# soldering.net
KiCad netlist of a schematic drawn in Altium Designer
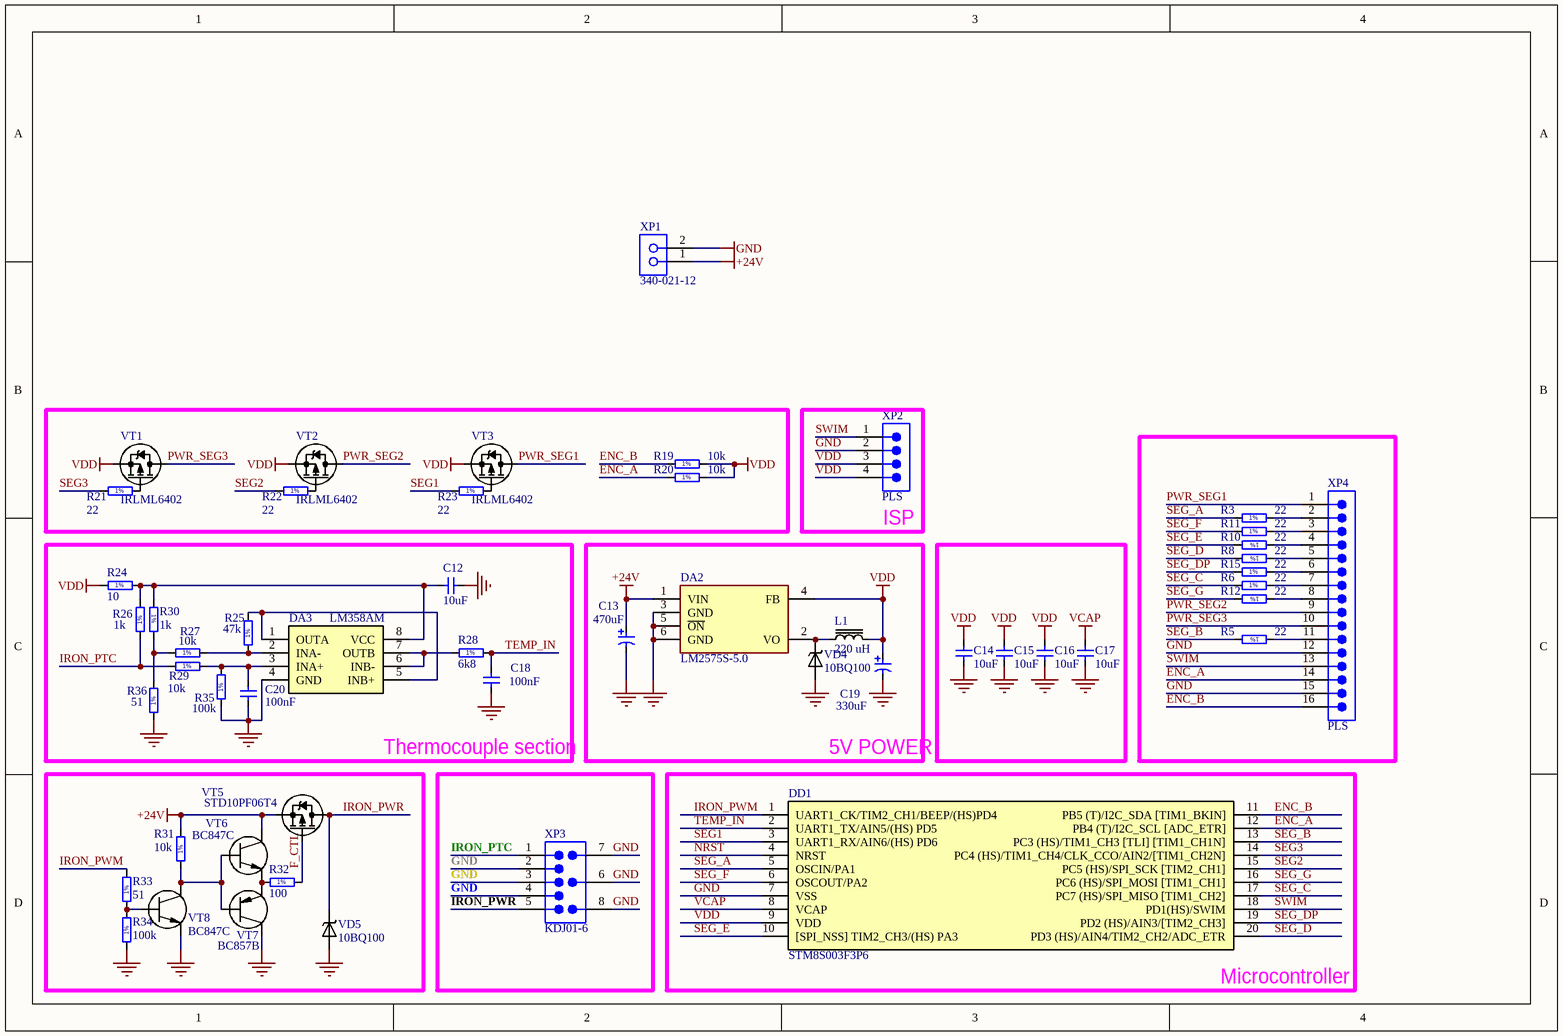
[diagram p0: soldering.SchDoc]

(export (version "E")
  (design (tool "Eeschema 10.0.6"))
  (components
    (comp (ref "C12")
      (value "10uF")
      (footprint "CAP0805R")
      (description "SMD 0805 Capacitor")
      (fields
        (field (name "PART NUMBER") "CC0805_10UF_10V_10%_X7R")
        (field (name "VOLTAGE") "10V")
        (field (name "AUTHOR") "I. Kuznetsov")
      )
      (libsource (lib "Capacitor") (part "CAP_NON_POLAR"))
    )
    (comp (ref "C13")
      (value "470uF")
      (footprint "CAP_EL_10_19_VERT")
      (fields (field (name "PART NUMBER") "SH050M0470B5S-1019 (VERT MOUNTED)") (field (name "VOLTAGE") "50V"))
      (libsource (lib "Capacitor") (part "CAP_POLAR"))
    )
    (comp (ref "C14")
      (value "10uF")
      (footprint "CAP0805R")
      (description "SMD 0805 Capacitor")
      (fields
        (field (name "PART NUMBER") "CC0805_10UF_10V_10%_X7R")
        (field (name "VOLTAGE") "10V")
        (field (name "AUTHOR") "I. Kuznetsov")
      )
      (libsource (lib "Capacitor") (part "CAP_NON_POLAR"))
    )
    (comp (ref "C15")
      (value "10uF")
      (footprint "CAP0805R")
      (description "SMD 0805 Capacitor")
      (fields
        (field (name "PART NUMBER") "CC0805_10UF_10V_10%_X7R")
        (field (name "VOLTAGE") "10V")
        (field (name "AUTHOR") "I. Kuznetsov")
      )
      (libsource (lib "Capacitor") (part "CAP_NON_POLAR"))
    )
    (comp (ref "C16")
      (value "10uF")
      (footprint "CAP0805R")
      (description "SMD 0805 Capacitor")
      (fields
        (field (name "PART NUMBER") "CC0805_10UF_10V_10%_X7R")
        (field (name "VOLTAGE") "10V")
        (field (name "AUTHOR") "I. Kuznetsov")
      )
      (libsource (lib "Capacitor") (part "CAP_NON_POLAR"))
    )
    (comp (ref "C17")
      (value "10uF")
      (footprint "CAP0805R")
      (description "SMD 0805 Capacitor")
      (fields
        (field (name "PART NUMBER") "CC0805_10UF_10V_10%_X7R")
        (field (name "VOLTAGE") "10V")
        (field (name "AUTHOR") "I. Kuznetsov")
      )
      (libsource (lib "Capacitor") (part "CAP_NON_POLAR"))
    )
    (comp (ref "C18")
      (value "100nF")
      (footprint "CAP0805R")
      (description "SMD 0805 Capacitor")
      (fields
        (field (name "PART NUMBER") "CC0805_100NF_50V_10%_X7R")
        (field (name "VOLTAGE") "50V")
        (field (name "AUTHOR") "I. Kuznetsov")
      )
      (libsource (lib "Capacitor") (part "CAP_NON_POLAR"))
    )
    (comp (ref "C19")
      (value "330uF")
      (footprint "TAN_D")
      (fields (field (name "PART NUMBER") "T495D337M010AHE100") (field (name "VOLTAGE") "10V"))
      (libsource (lib "Capacitor") (part "CAP_POLAR"))
    )
    (comp (ref "C20")
      (value "100nF")
      (footprint "CAP0805R")
      (description "SMD 0805 Capacitor")
      (fields
        (field (name "PART NUMBER") "CC0805_100NF_50V_10%_X7R")
        (field (name "VOLTAGE") "50V")
        (field (name "AUTHOR") "I. Kuznetsov")
      )
      (libsource (lib "Capacitor") (part "CAP_NON_POLAR"))
    )
    (comp (ref "DA2")
      (value "LM2575S-5.0")
      (footprint "TO-263-5")
      (fields (field (name "MANUFACTURER") "TI") (field (name "AUTHOR") "I. Kuznetsov"))
      (libsource (lib "IC And Semiconductor") (part "LM2575S"))
    )
    (comp (ref "DA3")
      (value "OP Amp")
      (footprint "SOP8")
      (fields (field (name "PARTNUMBER") "LM358AM"))
      (libsource (lib "tonometr") (part "LM358AM"))
    )
    (comp (ref "DD1")
      (value "8 Bit MCU")
      (footprint "TSSOP20")
      (description "8 Bit MCU (STmicroelectronics)")
      (fields (field (name "PARTNUMBER") "STM8S003F3P6"))
      (libsource (lib "soldering") (part "STM8S003F3P6"))
    )
    (comp (ref "L1")
      (value "220 uH")
      (footprint "SL1016")
      (fields (field (name "PART NUMBER") "SL1016T-4R7K-B-N") (field (name "TOLERANCE") "± 10%"))
      (libsource (lib "Transformer") (part "Core_Inductor"))
    )
    (comp (ref "R3")
      (value "22")
      (footprint "RES0805R")
      (fields
        (field (name "PART NUMBER") "R0805_22R_1%_0.125W_100PPM")
        (field (name "POWER") "0.125W")
        (field (name "TOLERANCE") "±1%")
        (field (name "AUTHOR") "CERN DEM JLC")
      )
      (libsource (lib "Resistor") (part "Resistor - 1%"))
    )
    (comp (ref "R5")
      (value "22")
      (footprint "RES0805R")
      (fields
        (field (name "PART NUMBER") "R0805_22R_1%_0.125W_100PPM")
        (field (name "POWER") "0.125W")
        (field (name "TOLERANCE") "±1%")
        (field (name "AUTHOR") "CERN DEM JLC")
      )
      (libsource (lib "Resistor") (part "Resistor - 1%"))
    )
    (comp (ref "R6")
      (value "22")
      (footprint "RES0805R")
      (fields
        (field (name "PART NUMBER") "R0805_22R_1%_0.125W_100PPM")
        (field (name "POWER") "0.125W")
        (field (name "TOLERANCE") "±1%")
        (field (name "AUTHOR") "CERN DEM JLC")
      )
      (libsource (lib "Resistor") (part "Resistor - 1%"))
    )
    (comp (ref "R8")
      (value "22")
      (footprint "RES0805R")
      (fields
        (field (name "PART NUMBER") "R0805_22R_1%_0.125W_100PPM")
        (field (name "POWER") "0.125W")
        (field (name "TOLERANCE") "±1%")
        (field (name "AUTHOR") "CERN DEM JLC")
      )
      (libsource (lib "Resistor") (part "Resistor - 1%"))
    )
    (comp (ref "R10")
      (value "22")
      (footprint "RES0805R")
      (fields
        (field (name "PART NUMBER") "R0805_22R_1%_0.125W_100PPM")
        (field (name "POWER") "0.125W")
        (field (name "TOLERANCE") "±1%")
        (field (name "AUTHOR") "CERN DEM JLC")
      )
      (libsource (lib "Resistor") (part "Resistor - 1%"))
    )
    (comp (ref "R11")
      (value "22")
      (footprint "RES0805R")
      (fields
        (field (name "PART NUMBER") "R0805_22R_1%_0.125W_100PPM")
        (field (name "POWER") "0.125W")
        (field (name "TOLERANCE") "±1%")
        (field (name "AUTHOR") "CERN DEM JLC")
      )
      (libsource (lib "Resistor") (part "Resistor - 1%"))
    )
    (comp (ref "R12")
      (value "22")
      (footprint "RES0805R")
      (fields
        (field (name "PART NUMBER") "R0805_22R_1%_0.125W_100PPM")
        (field (name "POWER") "0.125W")
        (field (name "TOLERANCE") "±1%")
        (field (name "AUTHOR") "CERN DEM JLC")
      )
      (libsource (lib "Resistor") (part "Resistor - 1%"))
    )
    (comp (ref "R15")
      (value "22")
      (footprint "RES0805R")
      (fields
        (field (name "PART NUMBER") "R0805_22R_1%_0.125W_100PPM")
        (field (name "POWER") "0.125W")
        (field (name "TOLERANCE") "±1%")
        (field (name "AUTHOR") "CERN DEM JLC")
      )
      (libsource (lib "Resistor") (part "Resistor - 1%"))
    )
    (comp (ref "R19")
      (value "10k")
      (footprint "RES0805R")
      (fields
        (field (name "PART NUMBER") "R0805_10K_1%_0.125W_100PPM")
        (field (name "POWER") "0.125W")
        (field (name "TOLERANCE") "±1%")
        (field (name "AUTHOR") "CERN DEM JLC")
      )
      (libsource (lib "Resistor") (part "Resistor - 1%"))
    )
    (comp (ref "R20")
      (value "10k")
      (footprint "RES0805R")
      (fields
        (field (name "PART NUMBER") "R0805_10K_1%_0.125W_100PPM")
        (field (name "POWER") "0.125W")
        (field (name "TOLERANCE") "±1%")
        (field (name "AUTHOR") "CERN DEM JLC")
      )
      (libsource (lib "Resistor") (part "Resistor - 1%"))
    )
    (comp (ref "R21")
      (value "22")
      (footprint "RES0805R")
      (fields
        (field (name "PART NUMBER") "R0805_22R_1%_0.125W_100PPM")
        (field (name "POWER") "0.125W")
        (field (name "TOLERANCE") "±1%")
        (field (name "AUTHOR") "CERN DEM JLC")
      )
      (libsource (lib "Resistor") (part "Resistor - 1%"))
    )
    (comp (ref "R22")
      (value "22")
      (footprint "RES0805R")
      (fields
        (field (name "PART NUMBER") "R0805_22R_1%_0.125W_100PPM")
        (field (name "POWER") "0.125W")
        (field (name "TOLERANCE") "±1%")
        (field (name "AUTHOR") "CERN DEM JLC")
      )
      (libsource (lib "Resistor") (part "Resistor - 1%"))
    )
    (comp (ref "R23")
      (value "22")
      (footprint "RES0805R")
      (fields
        (field (name "PART NUMBER") "R0805_22R_1%_0.125W_100PPM")
        (field (name "POWER") "0.125W")
        (field (name "TOLERANCE") "±1%")
        (field (name "AUTHOR") "CERN DEM JLC")
      )
      (libsource (lib "Resistor") (part "Resistor - 1%"))
    )
    (comp (ref "R24")
      (value "10")
      (footprint "RES0805R")
      (fields
        (field (name "PART NUMBER") "R0805_10R_1%_0.125W_200PPM")
        (field (name "POWER") "0.125W")
        (field (name "TOLERANCE") "±1%")
        (field (name "AUTHOR") "CERN DEM JLC")
      )
      (libsource (lib "Resistor") (part "Resistor - 1%"))
    )
    (comp (ref "R25")
      (value "47k")
      (footprint "RES0805R")
      (fields
        (field (name "PART NUMBER") "R0805_47K_1%_0.125W_100PPM")
        (field (name "POWER") "0.125W")
        (field (name "TOLERANCE") "±1%")
        (field (name "AUTHOR") "CERN DEM JLC")
      )
      (libsource (lib "Resistor") (part "Resistor - 1%"))
    )
    (comp (ref "R26")
      (value "1k")
      (footprint "RES0805R")
      (fields
        (field (name "PART NUMBER") "R0805_1K_1%_0.125W_100PPM")
        (field (name "POWER") "0.125W")
        (field (name "TOLERANCE") "±1%")
        (field (name "AUTHOR") "CERN DEM JLC")
      )
      (libsource (lib "Resistor") (part "Resistor - 1%"))
    )
    (comp (ref "R27")
      (value "10k")
      (footprint "RES0805R")
      (fields
        (field (name "PART NUMBER") "R0805_10K_1%_0.125W_100PPM")
        (field (name "POWER") "0.125W")
        (field (name "TOLERANCE") "±1%")
        (field (name "AUTHOR") "CERN DEM JLC")
      )
      (libsource (lib "Resistor") (part "Resistor - 1%"))
    )
    (comp (ref "R28")
      (value "6k8")
      (footprint "RES0805R")
      (fields
        (field (name "PART NUMBER") "R0805_6K8_1%_0.125W_100PPM")
        (field (name "POWER") "0.125W")
        (field (name "TOLERANCE") "±1%")
        (field (name "AUTHOR") "CERN DEM JLC")
      )
      (libsource (lib "Resistor") (part "Resistor - 1%"))
    )
    (comp (ref "R29")
      (value "10k")
      (footprint "RES0805R")
      (fields
        (field (name "PART NUMBER") "R0805_10K_1%_0.125W_100PPM")
        (field (name "POWER") "0.125W")
        (field (name "TOLERANCE") "±1%")
        (field (name "AUTHOR") "CERN DEM JLC")
      )
      (libsource (lib "Resistor") (part "Resistor - 1%"))
    )
    (comp (ref "R30")
      (value "1k")
      (footprint "RES0805R")
      (fields
        (field (name "PART NUMBER") "R0805_1K_1%_0.125W_100PPM")
        (field (name "POWER") "0.125W")
        (field (name "TOLERANCE") "±1%")
        (field (name "AUTHOR") "CERN DEM JLC")
      )
      (libsource (lib "Resistor") (part "Resistor - 1%"))
    )
    (comp (ref "R31")
      (value "10k")
      (footprint "RES0805R")
      (fields
        (field (name "PART NUMBER") "R0805_10K_1%_0.125W_100PPM")
        (field (name "POWER") "0.125W")
        (field (name "TOLERANCE") "±1%")
        (field (name "AUTHOR") "CERN DEM JLC")
      )
      (libsource (lib "Resistor") (part "Resistor - 1%"))
    )
    (comp (ref "R32")
      (value "100")
      (footprint "RES0805R")
      (fields
        (field (name "PART NUMBER") "R0805_100R_1%_0.125W_100PPM")
        (field (name "POWER") "0.125W")
        (field (name "TOLERANCE") "±1%")
        (field (name "AUTHOR") "CERN DEM JLC")
      )
      (libsource (lib "Resistor") (part "Resistor - 1%"))
    )
    (comp (ref "R33")
      (value "51")
      (footprint "RES0805R")
      (fields
        (field (name "PART NUMBER") "R0805_51R_1%_0.125W_100PPM")
        (field (name "POWER") "0.125W")
        (field (name "TOLERANCE") "±1%")
        (field (name "AUTHOR") "CERN DEM JLC")
      )
      (libsource (lib "Resistor") (part "Resistor - 1%"))
    )
    (comp (ref "R34")
      (value "100k")
      (footprint "RES0805R")
      (fields
        (field (name "PART NUMBER") "R0805_100K_1%_0.125W_100PPM")
        (field (name "POWER") "0.125W")
        (field (name "TOLERANCE") "±1%")
        (field (name "AUTHOR") "CERN DEM JLC")
      )
      (libsource (lib "Resistor") (part "Resistor - 1%"))
    )
    (comp (ref "R35")
      (value "100k")
      (footprint "RES0805R")
      (fields
        (field (name "PART NUMBER") "R0805_100K_1%_0.125W_100PPM")
        (field (name "MANUFACTURER") "GENERIC")
        (field (name "MANUFACTURER1 PART NUMBER") "NRC10F1003TRF")
        (field (name "AUTHOR") "CERN DEM JLC")
      )
      (libsource (lib "Resistor") (part "Resistor - 1%"))
    )
    (comp (ref "R36")
      (value "51")
      (footprint "RES0805R")
      (fields
        (field (name "PART NUMBER") "R0805_51R_1%_0.125W_100PPM")
        (field (name "POWER") "0.125W")
        (field (name "TOLERANCE") "±1%")
        (field (name "AUTHOR") "CERN DEM JLC")
      )
      (libsource (lib "Resistor") (part "Resistor - 1%"))
    )
    (comp (ref "VD4")
      (value "10BQ100")
      (footprint "DO-214AA")
      (fields (field (name "MANUFACTURER") "IR") (field (name "AUTHOR") "I. Kuznetsov"))
      (libsource (lib "IC And Semiconductor") (part "Diode - Schottky"))
    )
    (comp (ref "VD5")
      (value "10BQ100")
      (footprint "DO-214AA")
      (fields (field (name "MANUFACTURER") "IR") (field (name "AUTHOR") "I. Kuznetsov"))
      (libsource (lib "IC And Semiconductor") (part "Diode - Schottky"))
    )
    (comp (ref "VT1")
      (value "IRLML6402")
      (footprint "SOT23")
      (fields (field (name "AUTHOR") "I. Kuznetsov"))
      (libsource (lib "IC And Semiconductor") (part "P_CH_MOSFET"))
    )
    (comp (ref "VT2")
      (value "IRLML6402")
      (footprint "SOT23")
      (fields (field (name "AUTHOR") "I. Kuznetsov"))
      (libsource (lib "IC And Semiconductor") (part "P_CH_MOSFET"))
    )
    (comp (ref "VT3")
      (value "IRLML6402")
      (footprint "SOT23")
      (fields (field (name "AUTHOR") "I. Kuznetsov"))
      (libsource (lib "IC And Semiconductor") (part "P_CH_MOSFET"))
    )
    (comp (ref "VT5")
      (value "STD10PF06T4")
      (footprint "DPAK")
      (fields (field (name "AUTHOR") "I. Kuznetsov"))
      (libsource (lib "IC And Semiconductor") (part "P_CH_MOSFET"))
    )
    (comp (ref "VT6")
      (value "BC847C")
      (footprint "SOT23")
      (fields (field (name "AUTHOR") "I. Kuznetsov"))
      (libsource (lib "IC And Semiconductor") (part "NPN_BIPOLAR_SOT23"))
    )
    (comp (ref "VT7")
      (value "BC857B")
      (footprint "SOT23")
      (fields (field (name "AUTHOR") "I. Kuznetsov"))
      (libsource (lib "IC And Semiconductor") (part "PNP_BIPOLAR"))
    )
    (comp (ref "VT8")
      (value "BC847C")
      (footprint "SOT23")
      (fields (field (name "AUTHOR") "I. Kuznetsov"))
      (libsource (lib "IC And Semiconductor") (part "NPN_BIPOLAR_SOT23"))
    )
    (comp (ref "XP1")
      (value "340-021-12")
      (footprint "340-021-12")
      (libsource (lib "Connector") (part "CN_02S_1W"))
    )
    (comp (ref "XP2")
      (value "PLS")
      (footprint "PLS-04")
      (fields (field (name "PART NUMBER") "PLS-04") (field (name "MANUFACTURER") "AUK"))
      (libsource (lib "Connector") (part "CN_04P_1W"))
    )
    (comp (ref "XP3") (value "KDJ01-6") (footprint "KDJ01-6") (libsource (lib "Connector") (part "KDJ01-6")))
    (comp (ref "XP4")
      (value "PLS")
      (footprint "PLS-16")
      (fields (field (name "PART NUMBER") "PLS-16") (field (name "MANUFACTURER") "AUK"))
      (libsource (lib "Connector") (part "CN_16P_1W"))
    )
  )
  (nets
    (net (code "1") (name "+24V") (class "Default")
      (node (ref "C13") (pin "2") (pinfunction "2_2") (pintype "passive"))
      (node (ref "DA2") (pin "1") (pinfunction "VIN_1") (pintype "passive"))
      (node (ref "R31") (pin "2") (pinfunction "2_2") (pintype "passive"))
      (node (ref "VT5") (pin "2") (pinfunction "S_2") (pintype "passive"))
      (node (ref "VT6") (pin "3") (pinfunction "C_3") (pintype "passive"))
      (node (ref "XP1") (pin "1") (pinfunction "1_1") (pintype "passive"))
    )
    (net (code "2") (name "/ENC_A") (class "Default")
      (node (ref "DD1") (pin "12") (pinfunction "PB4_(T)/I2C_SCL_[ADC_ETR]_12") (pintype "passive"))
      (node (ref "R20") (pin "1") (pinfunction "1_1") (pintype "passive"))
      (node (ref "XP4") (pin "14") (pinfunction "14_14") (pintype "passive"))
    )
    (net (code "3") (name "/ENC_B") (class "Default")
      (node (ref "DD1") (pin "11") (pinfunction "PB5_(T)/I2C_SDA_[TIM1_BKIN]_11") (pintype "passive"))
      (node (ref "R19") (pin "1") (pinfunction "1_1") (pintype "passive"))
      (node (ref "XP4") (pin "16") (pinfunction "16_16") (pintype "passive"))
    )
    (net (code "4") (name "/F_CTL") (class "Default")
      (node (ref "R32") (pin "2") (pinfunction "2_2") (pintype "passive"))
      (node (ref "VT5") (pin "1") (pinfunction "G_1") (pintype "passive"))
    )
    (net (code "5") (name "/IRON_PTC") (class "Default")
      (node (ref "R26") (pin "1") (pinfunction "1_1") (pintype "passive"))
      (node (ref "R29") (pin "1") (pinfunction "1_1") (pintype "passive"))
      (node (ref "XP3") (pin "1") (pinfunction "1_1") (pintype "passive"))
    )
    (net (code "6") (name "/IRON_PWM") (class "Default")
      (node (ref "DD1") (pin "1") (pinfunction "UART1_CK/TIM2_CH1/BEEP/(HS)PD4_1") (pintype "passive"))
      (node (ref "R33") (pin "2") (pinfunction "2_2") (pintype "passive"))
    )
    (net (code "7") (name "/IRON_PWR") (class "Default")
      (node (ref "VD5") (pin "K") (pinfunction "K_K") (pintype "passive"))
      (node (ref "VT5") (pin "3") (pinfunction "D_3") (pintype "passive"))
      (node (ref "XP3") (pin "5") (pinfunction "5_5") (pintype "passive"))
    )
    (net (code "8") (name "/NRST") (class "Default")
      (node (ref "DD1") (pin "4") (pinfunction "NRST_4") (pintype "passive"))
    )
    (net (code "9") (name "/PWR_SEG1") (class "Default")
      (node (ref "VT3") (pin "3") (pinfunction "D_3") (pintype "passive"))
      (node (ref "XP4") (pin "1") (pinfunction "1_1") (pintype "passive"))
    )
    (net (code "10") (name "/PWR_SEG2") (class "Default")
      (node (ref "VT2") (pin "3") (pinfunction "D_3") (pintype "passive"))
      (node (ref "XP4") (pin "9") (pinfunction "9_9") (pintype "passive"))
    )
    (net (code "11") (name "/PWR_SEG3") (class "Default")
      (node (ref "VT1") (pin "3") (pinfunction "D_3") (pintype "passive"))
      (node (ref "XP4") (pin "10") (pinfunction "10_10") (pintype "passive"))
    )
    (net (code "12") (name "/SEG1") (class "Default")
      (node (ref "DD1") (pin "3") (pinfunction "UART1_RX/AIN6/(HS)_PD6_3") (pintype "passive"))
      (node (ref "R23") (pin "1") (pinfunction "1_1") (pintype "passive"))
    )
    (net (code "13") (name "/SEG2") (class "Default")
      (node (ref "DD1") (pin "15") (pinfunction "PC5_(HS)/SPI_SCK_[TIM2_CH1]_15") (pintype "passive"))
      (node (ref "R22") (pin "1") (pinfunction "1_1") (pintype "passive"))
    )
    (net (code "14") (name "/SEG3") (class "Default")
      (node (ref "DD1") (pin "14") (pinfunction "PC4_(HS)/TIM1_CH4/CLK_CCO/AIN2/[TIM1_CH2N]_14") (pintype "passive"))
      (node (ref "R21") (pin "1") (pinfunction "1_1") (pintype "passive"))
    )
    (net (code "15") (name "/SEG_A") (class "Default")
      (node (ref "DD1") (pin "5") (pinfunction "OSCIN/PA1_5") (pintype "passive"))
      (node (ref "R3") (pin "1") (pinfunction "1_1") (pintype "passive"))
    )
    (net (code "16") (name "/SEG_B") (class "Default")
      (node (ref "DD1") (pin "13") (pinfunction "PC3_(HS)/TIM1_CH3_[TLI]_[TIM1_CH1N]_13") (pintype "passive"))
      (node (ref "R5") (pin "2") (pinfunction "2_2") (pintype "passive"))
    )
    (net (code "17") (name "/SEG_C") (class "Default")
      (node (ref "DD1") (pin "17") (pinfunction "PC7_(HS)/SPI_MISO_[TIM1_CH2]_17") (pintype "passive"))
      (node (ref "R6") (pin "1") (pinfunction "1_1") (pintype "passive"))
    )
    (net (code "18") (name "/SEG_D") (class "Default")
      (node (ref "DD1") (pin "20") (pinfunction "PD3_(HS)/AIN4/TIM2_CH2/ADC_ETR_20") (pintype "passive"))
      (node (ref "R8") (pin "2") (pinfunction "2_2") (pintype "passive"))
    )
    (net (code "19") (name "/SEG_DP") (class "Default")
      (node (ref "DD1") (pin "19") (pinfunction "PD2_(HS)/AIN3/[TIM2_CH3]_19") (pintype "passive"))
      (node (ref "R15") (pin "1") (pinfunction "1_1") (pintype "passive"))
    )
    (net (code "20") (name "/SEG_E") (class "Default")
      (node (ref "DD1") (pin "10") (pinfunction "[SPI_NSS]_TIM2_CH3/(HS)_PA3_10") (pintype "passive"))
      (node (ref "R10") (pin "2") (pinfunction "2_2") (pintype "passive"))
    )
    (net (code "21") (name "/SEG_F") (class "Default")
      (node (ref "DD1") (pin "6") (pinfunction "OSCOUT/PA2_6") (pintype "passive"))
      (node (ref "R11") (pin "1") (pinfunction "1_1") (pintype "passive"))
    )
    (net (code "22") (name "/SEG_G") (class "Default")
      (node (ref "DD1") (pin "16") (pinfunction "PC6_(HS)/SPI_MOSI_[TIM1_CH1]_16") (pintype "passive"))
      (node (ref "R12") (pin "2") (pinfunction "2_2") (pintype "passive"))
    )
    (net (code "23") (name "/SWIM") (class "Default")
      (node (ref "DD1") (pin "18") (pinfunction "PD1(HS)/SWIM_18") (pintype "passive"))
      (node (ref "XP2") (pin "1") (pinfunction "1_1") (pintype "passive"))
      (node (ref "XP4") (pin "13") (pinfunction "13_13") (pintype "passive"))
    )
    (net (code "24") (name "/TEMP_IN") (class "Default")
      (node (ref "C18") (pin "2") (pinfunction "2_2") (pintype "passive"))
      (node (ref "DD1") (pin "2") (pinfunction "UART1_TX/AIN5/(HS)_PD5_2") (pintype "passive"))
      (node (ref "R28") (pin "2") (pinfunction "2_2") (pintype "passive"))
    )
    (net (code "25") (name "GND") (class "Default")
      (node (ref "C12") (pin "2") (pinfunction "2_2") (pintype "passive"))
      (node (ref "C13") (pin "1") (pinfunction "1_1") (pintype "passive"))
      (node (ref "C14") (pin "1") (pinfunction "1_1") (pintype "passive"))
      (node (ref "C15") (pin "1") (pinfunction "1_1") (pintype "passive"))
      (node (ref "C16") (pin "1") (pinfunction "1_1") (pintype "passive"))
      (node (ref "C17") (pin "1") (pinfunction "1_1") (pintype "passive"))
      (node (ref "C18") (pin "1") (pinfunction "1_1") (pintype "passive"))
      (node (ref "C19") (pin "1") (pinfunction "1_1") (pintype "passive"))
      (node (ref "C20") (pin "1") (pinfunction "1_1") (pintype "passive"))
      (node (ref "DA2") (pin "3") (pinfunction "GND_3") (pintype "passive"))
      (node (ref "DA2") (pin "5") (pinfunction "~{ON}_5") (pintype "passive"))
      (node (ref "DA2") (pin "6") (pinfunction "GND_6") (pintype "passive"))
      (node (ref "DA3") (pin "4") (pinfunction "GND_4") (pintype "passive"))
      (node (ref "DD1") (pin "7") (pinfunction "VSS_7") (pintype "passive"))
      (node (ref "R34") (pin "1") (pinfunction "1_1") (pintype "passive"))
      (node (ref "R35") (pin "1") (pinfunction "1_1") (pintype "passive"))
      (node (ref "R36") (pin "1") (pinfunction "1_1") (pintype "passive"))
      (node (ref "VD4") (pin "A") (pinfunction "A_A") (pintype "passive"))
      (node (ref "VD5") (pin "A") (pinfunction "A_A") (pintype "passive"))
      (node (ref "VT7") (pin "3") (pinfunction "C_3") (pintype "passive"))
      (node (ref "VT8") (pin "2") (pinfunction "E_2") (pintype "passive"))
      (node (ref "XP1") (pin "2") (pinfunction "2_2") (pintype "passive"))
      (node (ref "XP2") (pin "2") (pinfunction "2_2") (pintype "passive"))
      (node (ref "XP3") (pin "2") (pinfunction "2_2") (pintype "passive"))
      (node (ref "XP3") (pin "3") (pinfunction "3_3") (pintype "passive"))
      (node (ref "XP3") (pin "4") (pinfunction "4_4") (pintype "passive"))
      (node (ref "XP3") (pin "6") (pinfunction "6_6") (pintype "passive"))
      (node (ref "XP3") (pin "7") (pinfunction "7_7") (pintype "passive"))
      (node (ref "XP3") (pin "8") (pinfunction "8_8") (pintype "passive"))
      (node (ref "XP4") (pin "12") (pinfunction "12_12") (pintype "passive"))
      (node (ref "XP4") (pin "15") (pinfunction "15_15") (pintype "passive"))
    )
    (net (code "26") (name "Net-(DA2-VO)") (class "Default")
      (node (ref "DA2") (pin "2") (pinfunction "VO_2") (pintype "passive"))
      (node (ref "L1") (pin "1") (pinfunction "1_1") (pintype "passive"))
      (node (ref "VD4") (pin "K") (pinfunction "K_K") (pintype "passive"))
    )
    (net (code "27") (name "Net-(DA3-INA+)") (class "Default")
      (node (ref "C20") (pin "2") (pinfunction "2_2") (pintype "passive"))
      (node (ref "DA3") (pin "3") (pinfunction "INA+_3") (pintype "passive"))
      (node (ref "R29") (pin "2") (pinfunction "2_2") (pintype "passive"))
      (node (ref "R35") (pin "2") (pinfunction "2_2") (pintype "passive"))
    )
    (net (code "28") (name "Net-(DA3-INA-)") (class "Default")
      (node (ref "DA3") (pin "2") (pinfunction "INA-_2") (pintype "passive"))
      (node (ref "R25") (pin "1") (pinfunction "1_1") (pintype "passive"))
      (node (ref "R27") (pin "2") (pinfunction "2_2") (pintype "passive"))
    )
    (net (code "29") (name "Net-(DA3-INB+)") (class "Default")
      (node (ref "DA3") (pin "1") (pinfunction "OUTA_1") (pintype "passive"))
      (node (ref "DA3") (pin "5") (pinfunction "INB+_5") (pintype "passive"))
      (node (ref "R25") (pin "2") (pinfunction "2_2") (pintype "passive"))
    )
    (net (code "30") (name "Net-(DA3-INB-)") (class "Default")
      (node (ref "DA3") (pin "6") (pinfunction "INB-_6") (pintype "passive"))
      (node (ref "DA3") (pin "7") (pinfunction "OUTB_7") (pintype "passive"))
      (node (ref "R28") (pin "1") (pinfunction "1_1") (pintype "passive"))
    )
    (net (code "31") (name "Net-(DA3-VCC)") (class "Default")
      (node (ref "C12") (pin "1") (pinfunction "1_1") (pintype "passive"))
      (node (ref "DA3") (pin "8") (pinfunction "VCC_8") (pintype "passive"))
      (node (ref "R24") (pin "2") (pinfunction "2_2") (pintype "passive"))
      (node (ref "R26") (pin "2") (pinfunction "2_2") (pintype "passive"))
      (node (ref "R30") (pin "1") (pinfunction "1_1") (pintype "passive"))
    )
    (net (code "32") (name "Net-(R3-Pad2)") (class "Default")
      (node (ref "R3") (pin "2") (pinfunction "2_2") (pintype "passive"))
      (node (ref "XP4") (pin "2") (pinfunction "2_2") (pintype "passive"))
    )
    (net (code "33") (name "Net-(R5-Pad1)") (class "Default")
      (node (ref "R5") (pin "1") (pinfunction "1_1") (pintype "passive"))
      (node (ref "XP4") (pin "11") (pinfunction "11_11") (pintype "passive"))
    )
    (net (code "34") (name "Net-(R6-Pad2)") (class "Default")
      (node (ref "R6") (pin "2") (pinfunction "2_2") (pintype "passive"))
      (node (ref "XP4") (pin "7") (pinfunction "7_7") (pintype "passive"))
    )
    (net (code "35") (name "Net-(R8-Pad1)") (class "Default")
      (node (ref "R8") (pin "1") (pinfunction "1_1") (pintype "passive"))
      (node (ref "XP4") (pin "5") (pinfunction "5_5") (pintype "passive"))
    )
    (net (code "36") (name "Net-(R10-Pad1)") (class "Default")
      (node (ref "R10") (pin "1") (pinfunction "1_1") (pintype "passive"))
      (node (ref "XP4") (pin "4") (pinfunction "4_4") (pintype "passive"))
    )
    (net (code "37") (name "Net-(R11-Pad2)") (class "Default")
      (node (ref "R11") (pin "2") (pinfunction "2_2") (pintype "passive"))
      (node (ref "XP4") (pin "3") (pinfunction "3_3") (pintype "passive"))
    )
    (net (code "38") (name "Net-(R12-Pad1)") (class "Default")
      (node (ref "R12") (pin "1") (pinfunction "1_1") (pintype "passive"))
      (node (ref "XP4") (pin "8") (pinfunction "8_8") (pintype "passive"))
    )
    (net (code "39") (name "Net-(R15-Pad2)") (class "Default")
      (node (ref "R15") (pin "2") (pinfunction "2_2") (pintype "passive"))
      (node (ref "XP4") (pin "6") (pinfunction "6_6") (pintype "passive"))
    )
    (net (code "40") (name "Net-(R27-Pad1)") (class "Default")
      (node (ref "R27") (pin "1") (pinfunction "1_1") (pintype "passive"))
      (node (ref "R30") (pin "2") (pinfunction "2_2") (pintype "passive"))
      (node (ref "R36") (pin "2") (pinfunction "2_2") (pintype "passive"))
    )
    (net (code "41") (name "Net-(VT1-G)") (class "Default")
      (node (ref "R21") (pin "2") (pinfunction "2_2") (pintype "passive"))
      (node (ref "VT1") (pin "1") (pinfunction "G_1") (pintype "passive"))
    )
    (net (code "42") (name "Net-(VT2-G)") (class "Default")
      (node (ref "R22") (pin "2") (pinfunction "2_2") (pintype "passive"))
      (node (ref "VT2") (pin "1") (pinfunction "G_1") (pintype "passive"))
    )
    (net (code "43") (name "Net-(VT3-G)") (class "Default")
      (node (ref "R23") (pin "2") (pinfunction "2_2") (pintype "passive"))
      (node (ref "VT3") (pin "1") (pinfunction "G_1") (pintype "passive"))
    )
    (net (code "44") (name "Net-(VT6-B)") (class "Default")
      (node (ref "R31") (pin "1") (pinfunction "1_1") (pintype "passive"))
      (node (ref "VT6") (pin "1") (pinfunction "B_1") (pintype "passive"))
      (node (ref "VT7") (pin "1") (pinfunction "B_1") (pintype "passive"))
      (node (ref "VT8") (pin "3") (pinfunction "C_3") (pintype "passive"))
    )
    (net (code "45") (name "Net-(VT6-E)") (class "Default")
      (node (ref "R32") (pin "1") (pinfunction "1_1") (pintype "passive"))
      (node (ref "VT6") (pin "2") (pinfunction "E_2") (pintype "passive"))
      (node (ref "VT7") (pin "2") (pinfunction "E_2") (pintype "passive"))
    )
    (net (code "46") (name "Net-(VT8-B)") (class "Default")
      (node (ref "R33") (pin "1") (pinfunction "1_1") (pintype "passive"))
      (node (ref "R34") (pin "2") (pinfunction "2_2") (pintype "passive"))
      (node (ref "VT8") (pin "1") (pinfunction "B_1") (pintype "passive"))
    )
    (net (code "47") (name "VCAP") (class "Default")
      (node (ref "C17") (pin "2") (pinfunction "2_2") (pintype "passive"))
      (node (ref "DD1") (pin "8") (pinfunction "VCAP_8") (pintype "passive"))
    )
    (net (code "48") (name "VDD") (class "Default")
      (node (ref "C14") (pin "2") (pinfunction "2_2") (pintype "passive"))
      (node (ref "C15") (pin "2") (pinfunction "2_2") (pintype "passive"))
      (node (ref "C16") (pin "2") (pinfunction "2_2") (pintype "passive"))
      (node (ref "C19") (pin "2") (pinfunction "2_2") (pintype "passive"))
      (node (ref "DA2") (pin "4") (pinfunction "FB_4") (pintype "passive"))
      (node (ref "DD1") (pin "9") (pinfunction "VDD_9") (pintype "passive"))
      (node (ref "L1") (pin "2") (pinfunction "2_2") (pintype "passive"))
      (node (ref "R19") (pin "2") (pinfunction "2_2") (pintype "passive"))
      (node (ref "R20") (pin "2") (pinfunction "2_2") (pintype "passive"))
      (node (ref "R24") (pin "1") (pinfunction "1_1") (pintype "passive"))
      (node (ref "VT1") (pin "2") (pinfunction "S_2") (pintype "passive"))
      (node (ref "VT2") (pin "2") (pinfunction "S_2") (pintype "passive"))
      (node (ref "VT3") (pin "2") (pinfunction "S_2") (pintype "passive"))
      (node (ref "XP2") (pin "3") (pinfunction "3_3") (pintype "passive"))
      (node (ref "XP2") (pin "4") (pinfunction "4_4") (pintype "passive"))
    )
  )
)
